# 14_-RGMII_PHY.net
KiCad netlist of a schematic drawn in Altium Designer
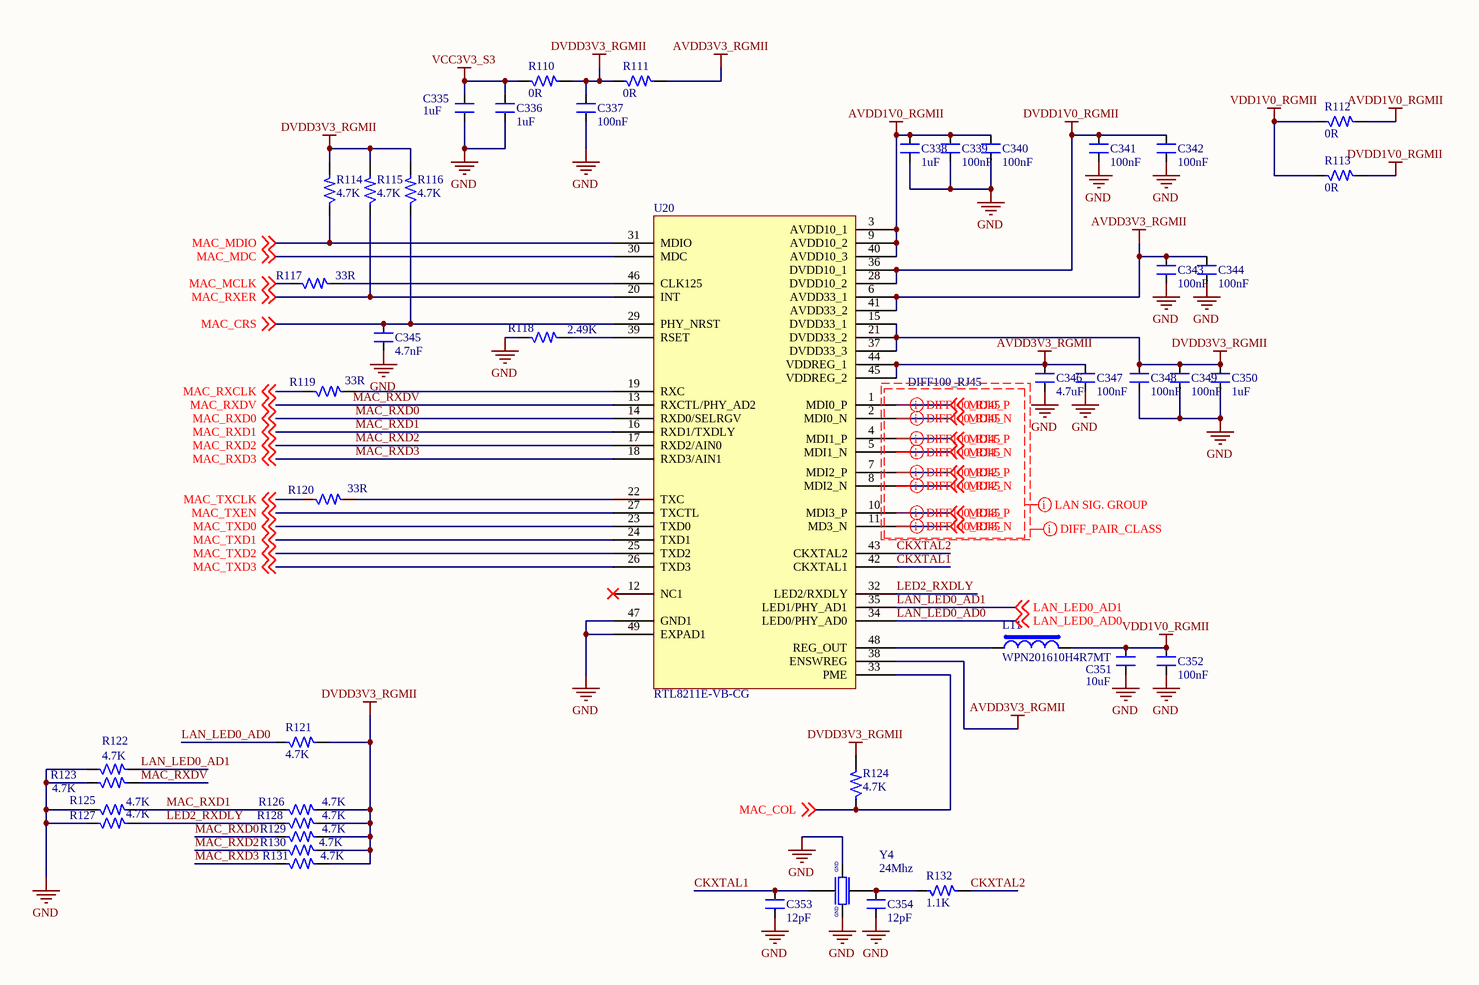
[diagram p0: [14]-RGMII_PHY.SchDoc]

(export (version "E")
  (design (tool "Eeschema 10.0.6"))
  (components
    (comp (ref "C335")
      (value "1uF")
      (footprint "CAP_0201")
      (description "1µF ±20% 16V Ceramic Capacitor X5R 0201 (0603 Metric)")
      (fields
        (field (name "MANUFACTURER") "Samsung Electro-Mechanics")
        (field (name "MANUFACTURER PART NUMBER") "CL03A105MO3NRNH")
      )
      (libsource (lib "EsteemPCB_SOM_Course_intlib") (part "CAP_1uF-16V-10%-0201"))
    )
    (comp (ref "C336")
      (value "1uF")
      (footprint "CAP_0201")
      (description "1µF ±20% 16V Ceramic Capacitor X5R 0201 (0603 Metric)")
      (fields
        (field (name "MANUFACTURER") "Samsung Electro-Mechanics")
        (field (name "MANUFACTURER PART NUMBER") "CL03A105MO3NRNH")
      )
      (libsource (lib "EsteemPCB_SOM_Course_intlib") (part "CAP_1uF-16V-10%-0201"))
    )
    (comp (ref "C337")
      (value "100nF")
      (footprint "CAP_0201")
      (description "0.1µF ±10% 25V Ceramic Capacitor X5R 0201 (0603 Metric)")
      (fields
        (field (name "MANUFACTURER") "TDK Corporation")
        (field (name "MANUFACTURER PART NUMBER") "C0603X5R1E104K030BB")
      )
      (libsource (lib "EsteemPCB_SOM_Course_intlib") (part "CAP_100nF-25V-10%-0201"))
    )
    (comp (ref "C338")
      (value "1uF")
      (footprint "CAP_0201")
      (description "1µF ±20% 16V Ceramic Capacitor X5R 0201 (0603 Metric)")
      (fields
        (field (name "MANUFACTURER") "Samsung Electro-Mechanics")
        (field (name "MANUFACTURER PART NUMBER") "CL03A105MO3NRNH")
      )
      (libsource (lib "EsteemPCB_SOM_Course_intlib") (part "CAP_1uF-16V-10%-0201"))
    )
    (comp (ref "C339")
      (value "100nF")
      (footprint "CAP_0201")
      (description "0.1µF ±10% 25V Ceramic Capacitor X5R 0201 (0603 Metric)")
      (fields
        (field (name "MANUFACTURER") "TDK Corporation")
        (field (name "MANUFACTURER PART NUMBER") "C0603X5R1E104K030BB")
      )
      (libsource (lib "EsteemPCB_SOM_Course_intlib") (part "CAP_100nF-25V-10%-0201"))
    )
    (comp (ref "C340")
      (value "100nF")
      (footprint "CAP_0201")
      (description "0.1µF ±10% 25V Ceramic Capacitor X5R 0201 (0603 Metric)")
      (fields
        (field (name "MANUFACTURER") "TDK Corporation")
        (field (name "MANUFACTURER PART NUMBER") "C0603X5R1E104K030BB")
      )
      (libsource (lib "EsteemPCB_SOM_Course_intlib") (part "CAP_100nF-25V-10%-0201"))
    )
    (comp (ref "C341")
      (value "100nF")
      (footprint "CAP_0201")
      (description "0.1µF ±10% 25V Ceramic Capacitor X5R 0201 (0603 Metric)")
      (fields
        (field (name "MANUFACTURER") "TDK Corporation")
        (field (name "MANUFACTURER PART NUMBER") "C0603X5R1E104K030BB")
      )
      (libsource (lib "EsteemPCB_SOM_Course_intlib") (part "CAP_100nF-25V-10%-0201"))
    )
    (comp (ref "C342")
      (value "100nF")
      (footprint "CAP_0201")
      (description "0.1µF ±10% 25V Ceramic Capacitor X5R 0201 (0603 Metric)")
      (fields
        (field (name "MANUFACTURER") "TDK Corporation")
        (field (name "MANUFACTURER PART NUMBER") "C0603X5R1E104K030BB")
      )
      (libsource (lib "EsteemPCB_SOM_Course_intlib") (part "CAP_100nF-25V-10%-0201"))
    )
    (comp (ref "C343")
      (value "100nF")
      (footprint "CAP_0201")
      (description "0.1µF ±10% 25V Ceramic Capacitor X5R 0201 (0603 Metric)")
      (fields
        (field (name "MANUFACTURER") "TDK Corporation")
        (field (name "MANUFACTURER PART NUMBER") "C0603X5R1E104K030BB")
      )
      (libsource (lib "EsteemPCB_SOM_Course_intlib") (part "CAP_100nF-25V-10%-0201"))
    )
    (comp (ref "C344")
      (value "100nF")
      (footprint "CAP_0201")
      (description "0.1µF ±10% 25V Ceramic Capacitor X5R 0201 (0603 Metric)")
      (fields
        (field (name "MANUFACTURER") "TDK Corporation")
        (field (name "MANUFACTURER PART NUMBER") "C0603X5R1E104K030BB")
      )
      (libsource (lib "EsteemPCB_SOM_Course_intlib") (part "CAP_100nF-25V-10%-0201"))
    )
    (comp (ref "C345")
      (value "4.7nF")
      (footprint "CAP_0201")
      (description "4700pF ±10% 10V Ceramic Capacitor X7R 0201 (0603 Metric)")
      (fields
        (field (name "MANUFACTURER") "AVX Corporation")
        (field (name "MANUFACTURER PART NUMBER") "0201ZC472KAT2A")
      )
      (libsource (lib "EsteemPCB_SOM_Course_intlib") (part "CAP_4.7nF-10V-10%-0201"))
    )
    (comp (ref "C346")
      (value "4.7uF")
      (footprint "CAP_0201")
      (description "4.7µF ±20% 6.3V Ceramic Capacitor X5R 0201 (0603 Metric)")
      (fields
        (field (name "MANUFACTURER") "Murata Electronics")
        (field (name "MANUFACTURER PART NUMBER") "GRM035R60J475ME15D")
      )
      (libsource (lib "EsteemPCB_SOM_Course_intlib") (part "CAP_4.7uF-6.3V-20%-0201"))
    )
    (comp (ref "C347")
      (value "100nF")
      (footprint "CAP_0201")
      (description "0.1µF ±10% 25V Ceramic Capacitor X5R 0201 (0603 Metric)")
      (fields
        (field (name "MANUFACTURER") "TDK Corporation")
        (field (name "MANUFACTURER PART NUMBER") "C0603X5R1E104K030BB")
      )
      (libsource (lib "EsteemPCB_SOM_Course_intlib") (part "CAP_100nF-25V-10%-0201"))
    )
    (comp (ref "C348")
      (value "100nF")
      (footprint "CAP_0201")
      (description "0.1µF ±10% 25V Ceramic Capacitor X5R 0201 (0603 Metric)")
      (fields
        (field (name "MANUFACTURER") "TDK Corporation")
        (field (name "MANUFACTURER PART NUMBER") "C0603X5R1E104K030BB")
      )
      (libsource (lib "EsteemPCB_SOM_Course_intlib") (part "CAP_100nF-25V-10%-0201"))
    )
    (comp (ref "C349")
      (value "100nF")
      (footprint "CAP_0201")
      (description "0.1µF ±10% 25V Ceramic Capacitor X5R 0201 (0603 Metric)")
      (fields
        (field (name "MANUFACTURER") "TDK Corporation")
        (field (name "MANUFACTURER PART NUMBER") "C0603X5R1E104K030BB")
      )
      (libsource (lib "EsteemPCB_SOM_Course_intlib") (part "CAP_100nF-25V-10%-0201"))
    )
    (comp (ref "C350")
      (value "1uF")
      (footprint "CAP_0603")
      (description "1µF ±10% 10V Ceramic Capacitor X5R 0603 (1608 Metric)")
      (fields
        (field (name "MANUFACTURER") "Samsung Electro-Mechanics")
        (field (name "MANUFACTURER PART NUMBER") "CL10A105KP8NNNC")
      )
      (libsource (lib "RK3399 _Module_Schlib") (part "CAP_1uF-10V-5%-0603"))
    )
    (comp (ref "C351")
      (value "10uF")
      (footprint "CAP_0402")
      (description "10µF ±20% 10V Ceramic Capacitor X5R 0402 (1005 Metric)")
      (fields
        (field (name "MANUFACTURER PART NUMBER") "CL05A106MP5NUNC")
        (field (name "MANUFACTURER") "Samsung Electro-Mechanics")
      )
      (libsource (lib "EsteemPCB_SOM_Course_intlib") (part "CAP_10uF-10V-20%-0402"))
    )
    (comp (ref "C352")
      (value "100nF")
      (footprint "CAP_0201")
      (description "0.1µF ±10% 25V Ceramic Capacitor X5R 0201 (0603 Metric)")
      (fields
        (field (name "MANUFACTURER") "TDK Corporation")
        (field (name "MANUFACTURER PART NUMBER") "C0603X5R1E104K030BB")
      )
      (libsource (lib "EsteemPCB_SOM_Course_intlib") (part "CAP_100nF-25V-10%-0201"))
    )
    (comp (ref "C353")
      (value "12pF")
      (footprint "CAP_0201")
      (description "12pF ±10% 16V Ceramic Capacitor C0G, NP0 0201 (0603 Metric)")
      (fields
        (field (name "MANUFACTURER") "AVX Corporation")
        (field (name "MANUFACTURER PART NUMBER") "0201YA120KAT2A")
      )
      (libsource (lib "EsteemPCB_SOM_Course_intlib") (part "CAP_12pF-16V-10%-0201"))
    )
    (comp (ref "C354")
      (value "12pF")
      (footprint "CAP_0201")
      (description "12pF ±10% 16V Ceramic Capacitor C0G, NP0 0201 (0603 Metric)")
      (fields
        (field (name "MANUFACTURER") "AVX Corporation")
        (field (name "MANUFACTURER PART NUMBER") "0201YA120KAT2A")
      )
      (libsource (lib "EsteemPCB_SOM_Course_intlib") (part "CAP_12pF-16V-10%-0201"))
    )
    (comp (ref "L11")
      (value "WPN201610H4R7MT")
      (footprint "IND_62.9_110X86.6_SMD")
      (description "4.7uH ±20% 900mA 425mΩ SMD,2.0x1.6x1.0mm Power Inductors RoHS")
      (fields (field (name "MANUFACTURER") "Sunlord"))
      (libsource (lib "RK3399 _Module_Schlib") (part "IND_4.7uH-0.9A-20%-SMD"))
    )
    (comp (ref "R110")
      (value "0R")
      (footprint "RES_0201")
      (description "0 Ohms Jumper 0.05W, 1/20W Chip Resistor 0201 (0603 Metric) Automotive AEC-Q200 Thick Film")
      (fields
        (field (name "MANUFACTURER") "Bourns Inc.")
        (field (name "MANUFACTURER PART NUMBER") "CR0201AJ/-000GLF")
      )
      (libsource (lib "EsteemPCB_SOM_Course_intlib") (part "RES_0R-0.05W-1%-0201"))
    )
    (comp (ref "R111")
      (value "0R")
      (footprint "RES_0201")
      (description "0 Ohms Jumper 0.05W, 1/20W Chip Resistor 0201 (0603 Metric) Automotive AEC-Q200 Thick Film")
      (fields
        (field (name "MANUFACTURER") "Bourns Inc.")
        (field (name "MANUFACTURER PART NUMBER") "CR0201AJ/-000GLF")
      )
      (libsource (lib "EsteemPCB_SOM_Course_intlib") (part "RES_0R-0.05W-1%-0201"))
    )
    (comp (ref "R112")
      (value "0R")
      (footprint "RES_0201")
      (description "0 Ohms Jumper 0.05W, 1/20W Chip Resistor 0201 (0603 Metric) Automotive AEC-Q200 Thick Film")
      (fields
        (field (name "MANUFACTURER") "Bourns Inc.")
        (field (name "MANUFACTURER PART NUMBER") "CR0201AJ/-000GLF")
      )
      (libsource (lib "EsteemPCB_SOM_Course_intlib") (part "RES_0R-0.05W-1%-0201"))
    )
    (comp (ref "R113")
      (value "0R")
      (footprint "RES_0201")
      (description "0 Ohms Jumper 0.05W, 1/20W Chip Resistor 0201 (0603 Metric) Automotive AEC-Q200 Thick Film")
      (fields
        (field (name "MANUFACTURER") "Bourns Inc.")
        (field (name "MANUFACTURER PART NUMBER") "CR0201AJ/-000GLF")
      )
      (libsource (lib "EsteemPCB_SOM_Course_intlib") (part "RES_0R-0.05W-1%-0201"))
    )
    (comp (ref "R114")
      (value "4.7K")
      (footprint "RES_0201")
      (description "4.02 kOhms ±1% 0.05W, 1/20W Chip Resistor 0201 (0603 Metric) Thick Film")
      (fields
        (field (name "MANUFACTURER") "Yageo")
        (field (name "MANUFACTURER PART NUMBER") "RC0201FR-074K02L")
      )
      (libsource (lib "EsteemPCB_SOM_Course_intlib") (part "RES_4.7K-0.1W-1%-0201"))
    )
    (comp (ref "R115")
      (value "4.7K")
      (footprint "RES_0201")
      (description "4.02 kOhms ±1% 0.05W, 1/20W Chip Resistor 0201 (0603 Metric) Thick Film")
      (fields
        (field (name "MANUFACTURER") "Yageo")
        (field (name "MANUFACTURER PART NUMBER") "RC0201FR-074K02L")
      )
      (libsource (lib "EsteemPCB_SOM_Course_intlib") (part "RES_4.7K-0.1W-1%-0201"))
    )
    (comp (ref "R116")
      (value "4.7K")
      (footprint "RES_0201")
      (description "4.02 kOhms ±1% 0.05W, 1/20W Chip Resistor 0201 (0603 Metric) Thick Film")
      (fields
        (field (name "MANUFACTURER") "Yageo")
        (field (name "MANUFACTURER PART NUMBER") "RC0201FR-074K02L")
      )
      (libsource (lib "EsteemPCB_SOM_Course_intlib") (part "RES_4.7K-0.1W-1%-0201"))
    )
    (comp (ref "R117")
      (value "33R")
      (footprint "RES_0201")
      (description "33 Ohms ±1% 0.05W, 1/20W Chip Resistor 0201 (0603 Metric) Thick Film")
      (fields
        (field (name "MANUFACTURER") "Yageo")
        (field (name "MANUFACTURER PART NUMBER") "RC0201FR-0733RL")
      )
      (libsource (lib "EsteemPCB_SOM_Course_intlib") (part "RES_33R-0.05W-1%-0201"))
    )
    (comp (ref "R118")
      (value "2.49K")
      (footprint "RES_0201")
      (description "2.49 kOhms ±1% 0.05W, 1/20W Chip Resistor 0201 (0603 Metric) Automotive AEC-Q200 Thick Film")
      (fields
        (field (name "MANUFACTURER") "Panasonic Electronic Components")
        (field (name "MANUFACTURER PART NUMBER") "ERJ-1GNF2491C")
      )
      (libsource (lib "EsteemPCB_SOM_Course_intlib") (part "RES_2.49K-0.05W-1%-0201"))
    )
    (comp (ref "R119")
      (value "33R")
      (footprint "RES_0201")
      (description "33 Ohms ±1% 0.05W, 1/20W Chip Resistor 0201 (0603 Metric) Thick Film")
      (fields
        (field (name "MANUFACTURER") "Yageo")
        (field (name "MANUFACTURER PART NUMBER") "RC0201FR-0733RL")
      )
      (libsource (lib "EsteemPCB_SOM_Course_intlib") (part "RES_33R-0.05W-1%-0201"))
    )
    (comp (ref "R120")
      (value "33R")
      (footprint "RES_0201")
      (description "33 Ohms ±1% 0.05W, 1/20W Chip Resistor 0201 (0603 Metric) Thick Film")
      (fields
        (field (name "MANUFACTURER") "Yageo")
        (field (name "MANUFACTURER PART NUMBER") "RC0201FR-0733RL")
      )
      (libsource (lib "EsteemPCB_SOM_Course_intlib") (part "RES_33R-0.05W-1%-0201"))
    )
    (comp (ref "R121")
      (value "4.7K")
      (footprint "RES_0201")
      (description "4.02 kOhms ±1% 0.05W, 1/20W Chip Resistor 0201 (0603 Metric) Thick Film")
      (fields
        (field (name "MANUFACTURER") "Yageo")
        (field (name "MANUFACTURER PART NUMBER") "RC0201FR-074K02L")
      )
      (libsource (lib "EsteemPCB_SOM_Course_intlib") (part "RES_4.7K-0.1W-1%-0201"))
    )
    (comp (ref "R122")
      (value "4.7K")
      (footprint "RES_0201")
      (description "4.02 kOhms ±1% 0.05W, 1/20W Chip Resistor 0201 (0603 Metric) Thick Film")
      (fields
        (field (name "MANUFACTURER") "Yageo")
        (field (name "MANUFACTURER PART NUMBER") "RC0201FR-074K02L")
      )
      (libsource (lib "EsteemPCB_SOM_Course_intlib") (part "RES_4.7K-0.1W-1%-0201"))
    )
    (comp (ref "R123")
      (value "4.7K")
      (footprint "RES_0201")
      (description "4.02 kOhms ±1% 0.05W, 1/20W Chip Resistor 0201 (0603 Metric) Thick Film")
      (fields
        (field (name "MANUFACTURER") "Yageo")
        (field (name "MANUFACTURER PART NUMBER") "RC0201FR-074K02L")
      )
      (libsource (lib "EsteemPCB_SOM_Course_intlib") (part "RES_4.7K-0.1W-1%-0201"))
    )
    (comp (ref "R124")
      (value "4.7K")
      (footprint "RES_0201")
      (description "4.02 kOhms ±1% 0.05W, 1/20W Chip Resistor 0201 (0603 Metric) Thick Film")
      (fields
        (field (name "MANUFACTURER") "Yageo")
        (field (name "MANUFACTURER PART NUMBER") "RC0201FR-074K02L")
      )
      (libsource (lib "EsteemPCB_SOM_Course_intlib") (part "RES_4.7K-0.1W-1%-0201"))
    )
    (comp (ref "R125")
      (value "4.7K")
      (footprint "RES_0201")
      (description "4.02 kOhms ±1% 0.05W, 1/20W Chip Resistor 0201 (0603 Metric) Thick Film")
      (fields
        (field (name "MANUFACTURER") "Yageo")
        (field (name "MANUFACTURER PART NUMBER") "RC0201FR-074K02L")
      )
      (libsource (lib "EsteemPCB_SOM_Course_intlib") (part "RES_4.7K-0.1W-1%-0201"))
    )
    (comp (ref "R126")
      (value "4.7K")
      (footprint "RES_0201")
      (description "4.02 kOhms ±1% 0.05W, 1/20W Chip Resistor 0201 (0603 Metric) Thick Film")
      (fields
        (field (name "MANUFACTURER") "Yageo")
        (field (name "MANUFACTURER PART NUMBER") "RC0201FR-074K02L")
      )
      (libsource (lib "EsteemPCB_SOM_Course_intlib") (part "RES_4.7K-0.1W-1%-0201"))
    )
    (comp (ref "R127")
      (value "4.7K")
      (footprint "RES_0201")
      (description "4.02 kOhms ±1% 0.05W, 1/20W Chip Resistor 0201 (0603 Metric) Thick Film")
      (fields
        (field (name "MANUFACTURER") "Yageo")
        (field (name "MANUFACTURER PART NUMBER") "RC0201FR-074K02L")
      )
      (libsource (lib "EsteemPCB_SOM_Course_intlib") (part "RES_4.7K-0.1W-1%-0201"))
    )
    (comp (ref "R128")
      (value "4.7K")
      (footprint "RES_0201")
      (description "4.02 kOhms ±1% 0.05W, 1/20W Chip Resistor 0201 (0603 Metric) Thick Film")
      (fields
        (field (name "MANUFACTURER") "Yageo")
        (field (name "MANUFACTURER PART NUMBER") "RC0201FR-074K02L")
      )
      (libsource (lib "EsteemPCB_SOM_Course_intlib") (part "RES_4.7K-0.1W-1%-0201"))
    )
    (comp (ref "R129")
      (value "4.7K")
      (footprint "RES_0201")
      (description "4.02 kOhms ±1% 0.05W, 1/20W Chip Resistor 0201 (0603 Metric) Thick Film")
      (fields
        (field (name "MANUFACTURER") "Yageo")
        (field (name "MANUFACTURER PART NUMBER") "RC0201FR-074K02L")
      )
      (libsource (lib "EsteemPCB_SOM_Course_intlib") (part "RES_4.7K-0.1W-1%-0201"))
    )
    (comp (ref "R130")
      (value "4.7K")
      (footprint "RES_0201")
      (description "4.02 kOhms ±1% 0.05W, 1/20W Chip Resistor 0201 (0603 Metric) Thick Film")
      (fields
        (field (name "MANUFACTURER") "Yageo")
        (field (name "MANUFACTURER PART NUMBER") "RC0201FR-074K02L")
      )
      (libsource (lib "EsteemPCB_SOM_Course_intlib") (part "RES_4.7K-0.1W-1%-0201"))
    )
    (comp (ref "R131")
      (value "4.7K")
      (footprint "RES_0201")
      (description "4.02 kOhms ±1% 0.05W, 1/20W Chip Resistor 0201 (0603 Metric) Thick Film")
      (fields
        (field (name "MANUFACTURER") "Yageo")
        (field (name "MANUFACTURER PART NUMBER") "RC0201FR-074K02L")
      )
      (libsource (lib "EsteemPCB_SOM_Course_intlib") (part "RES_4.7K-0.1W-1%-0201"))
    )
    (comp (ref "R132")
      (value "1.1K")
      (footprint "RES_0201")
      (description "1.1 kOhms ±1% 0.05W, 1/20W Chip Resistor 0201 (0603 Metric) Automotive AEC-Q200 Thick Film")
      (fields
        (field (name "MANUFACTURER") "Panasonic Electronic Components")
        (field (name "MANUFACTURER PART NUMBER") "ERJ-1GNF1101C")
      )
      (libsource (lib "EsteemPCB_SOM_Course_intlib") (part "RES_1.1K-0.05W-1%-0201"))
    )
    (comp (ref "U20")
      (value "RTL8211E-VB-CG")
      (footprint "QFN48_19.6_324X324_SMD")
      (fields (field (name "MANUFACTURER") "Realtek Semicon"))
      (libsource (lib "RK3399 _Module_Schlib") (part "IC_RTL8211E-VB-CG"))
    )
    (comp (ref "Y4")
      (value "24Mhz")
      (footprint "XTAL_ABM8AIG-24.000MHZ-12-2Z-T3")
      (description "24MHz ±20ppm Crystal 12pF 50 Ohms 4-SMD, No Lead")
      (fields
        (field (name "MANUFACTURER") "Abracon LLC")
        (field (name "MANUFACTURER PART NUMBER") "ABM8AIG-24.000MHZ-12-2Z-T3")
      )
      (libsource (lib "RK3399 _Module_Schlib") (part "XTAL_24Mhz-12pF-4-SMD"))
    )
  )
  (nets
    (net (code "1") (name "/CKXTAL1") (class "Default")
      (node (ref "C353") (pin "2") (pinfunction "2_2") (pintype "passive"))
      (node (ref "U20") (pin "42") (pinfunction "CKXTAL1_42") (pintype "passive"))
      (node (ref "Y4") (pin "1") (pinfunction "1_1") (pintype "passive"))
    )
    (net (code "2") (name "/CKXTAL2") (class "Default")
      (node (ref "R132") (pin "2") (pinfunction "2_2") (pintype "passive"))
      (node (ref "U20") (pin "43") (pinfunction "CKXTAL2_43") (pintype "passive"))
    )
    (net (code "3") (name "/LED2_RXDLY") (class "Default")
      (node (ref "R127") (pin "2") (pinfunction "2_2") (pintype "passive"))
      (node (ref "R128") (pin "1") (pinfunction "1_1") (pintype "passive"))
      (node (ref "U20") (pin "32") (pinfunction "LED2/RXDLY_32") (pintype "passive"))
    )
    (net (code "4") (name "AVDD1V0_RGMII") (class "Default")
      (node (ref "C338") (pin "2") (pinfunction "2_2") (pintype "passive"))
      (node (ref "C339") (pin "2") (pinfunction "2_2") (pintype "passive"))
      (node (ref "C340") (pin "2") (pinfunction "2_2") (pintype "passive"))
      (node (ref "R112") (pin "2") (pinfunction "2_2") (pintype "passive"))
      (node (ref "U20") (pin "3") (pinfunction "AVDD10_1_3") (pintype "passive"))
      (node (ref "U20") (pin "40") (pinfunction "AVDD10_3_40") (pintype "passive"))
      (node (ref "U20") (pin "9") (pinfunction "AVDD10_2_9") (pintype "passive"))
    )
    (net (code "5") (name "AVDD3V3_RGMII") (class "Default")
      (node (ref "C343") (pin "2") (pinfunction "2_2") (pintype "passive"))
      (node (ref "C344") (pin "2") (pinfunction "2_2") (pintype "passive"))
      (node (ref "C346") (pin "2") (pinfunction "2_2") (pintype "passive"))
      (node (ref "C347") (pin "2") (pinfunction "2_2") (pintype "passive"))
      (node (ref "R111") (pin "2") (pinfunction "2_2") (pintype "passive"))
      (node (ref "U20") (pin "38") (pinfunction "ENSWREG_38") (pintype "passive"))
      (node (ref "U20") (pin "41") (pinfunction "AVDD33_2_41") (pintype "passive"))
      (node (ref "U20") (pin "44") (pinfunction "VDDREG_1_44") (pintype "passive"))
      (node (ref "U20") (pin "45") (pinfunction "VDDREG_2_45") (pintype "passive"))
      (node (ref "U20") (pin "6") (pinfunction "AVDD33_1_6") (pintype "passive"))
    )
    (net (code "6") (name "DVDD1V0_RGMII") (class "Default")
      (node (ref "C341") (pin "2") (pinfunction "2_2") (pintype "passive"))
      (node (ref "C342") (pin "2") (pinfunction "2_2") (pintype "passive"))
      (node (ref "R113") (pin "2") (pinfunction "2_2") (pintype "passive"))
      (node (ref "U20") (pin "28") (pinfunction "DVDD10_2_28") (pintype "passive"))
      (node (ref "U20") (pin "36") (pinfunction "DVDD10_1_36") (pintype "passive"))
    )
    (net (code "7") (name "DVDD3V3_RGMII") (class "Default")
      (node (ref "C337") (pin "2") (pinfunction "2_2") (pintype "passive"))
      (node (ref "C348") (pin "2") (pinfunction "2_2") (pintype "passive"))
      (node (ref "C349") (pin "2") (pinfunction "2_2") (pintype "passive"))
      (node (ref "C350") (pin "2") (pinfunction "2_2") (pintype "passive"))
      (node (ref "R110") (pin "2") (pinfunction "2_2") (pintype "passive"))
      (node (ref "R111") (pin "1") (pinfunction "1_1") (pintype "passive"))
      (node (ref "R114") (pin "2") (pinfunction "2_2") (pintype "passive"))
      (node (ref "R115") (pin "2") (pinfunction "2_2") (pintype "passive"))
      (node (ref "R116") (pin "2") (pinfunction "2_2") (pintype "passive"))
      (node (ref "R121") (pin "2") (pinfunction "2_2") (pintype "passive"))
      (node (ref "R124") (pin "2") (pinfunction "2_2") (pintype "passive"))
      (node (ref "R126") (pin "2") (pinfunction "2_2") (pintype "passive"))
      (node (ref "R128") (pin "2") (pinfunction "2_2") (pintype "passive"))
      (node (ref "R129") (pin "2") (pinfunction "2_2") (pintype "passive"))
      (node (ref "R130") (pin "2") (pinfunction "2_2") (pintype "passive"))
      (node (ref "R131") (pin "2") (pinfunction "2_2") (pintype "passive"))
      (node (ref "U20") (pin "15") (pinfunction "DVDD33_1_15") (pintype "passive"))
      (node (ref "U20") (pin "21") (pinfunction "DVDD33_2_21") (pintype "passive"))
      (node (ref "U20") (pin "37") (pinfunction "DVDD33_3_37") (pintype "passive"))
    )
    (net (code "8") (name "GND") (class "Default")
      (node (ref "C335") (pin "1") (pinfunction "1_1") (pintype "passive"))
      (node (ref "C336") (pin "1") (pinfunction "1_1") (pintype "passive"))
      (node (ref "C337") (pin "1") (pinfunction "1_1") (pintype "passive"))
      (node (ref "C338") (pin "1") (pinfunction "1_1") (pintype "passive"))
      (node (ref "C339") (pin "1") (pinfunction "1_1") (pintype "passive"))
      (node (ref "C340") (pin "1") (pinfunction "1_1") (pintype "passive"))
      (node (ref "C341") (pin "1") (pinfunction "1_1") (pintype "passive"))
      (node (ref "C342") (pin "1") (pinfunction "1_1") (pintype "passive"))
      (node (ref "C343") (pin "1") (pinfunction "1_1") (pintype "passive"))
      (node (ref "C344") (pin "1") (pinfunction "1_1") (pintype "passive"))
      (node (ref "C345") (pin "1") (pinfunction "1_1") (pintype "passive"))
      (node (ref "C346") (pin "1") (pinfunction "1_1") (pintype "passive"))
      (node (ref "C347") (pin "1") (pinfunction "1_1") (pintype "passive"))
      (node (ref "C348") (pin "1") (pinfunction "1_1") (pintype "passive"))
      (node (ref "C349") (pin "1") (pinfunction "1_1") (pintype "passive"))
      (node (ref "C350") (pin "1") (pinfunction "1_1") (pintype "passive"))
      (node (ref "C351") (pin "1") (pinfunction "1_1") (pintype "passive"))
      (node (ref "C352") (pin "1") (pinfunction "1_1") (pintype "passive"))
      (node (ref "C353") (pin "1") (pinfunction "1_1") (pintype "passive"))
      (node (ref "C354") (pin "1") (pinfunction "1_1") (pintype "passive"))
      (node (ref "R118") (pin "1") (pinfunction "1_1") (pintype "passive"))
      (node (ref "R122") (pin "1") (pinfunction "1_1") (pintype "passive"))
      (node (ref "R123") (pin "1") (pinfunction "1_1") (pintype "passive"))
      (node (ref "R125") (pin "1") (pinfunction "1_1") (pintype "passive"))
      (node (ref "R127") (pin "1") (pinfunction "1_1") (pintype "passive"))
      (node (ref "U20") (pin "47") (pinfunction "GND1_47") (pintype "passive"))
      (node (ref "U20") (pin "49") (pinfunction "EXPAD1_49") (pintype "passive"))
      (node (ref "Y4") (pin "2") (pinfunction "2_2") (pintype "passive"))
      (node (ref "Y4") (pin "4") (pinfunction "4_4") (pintype "passive"))
    )
    (net (code "9") (name "LAN_LED0_AD0") (class "Default")
      (node (ref "R121") (pin "1") (pinfunction "1_1") (pintype "passive"))
      (node (ref "U20") (pin "34") (pinfunction "LED0/PHY_AD0_34") (pintype "passive"))
    )
    (net (code "10") (name "LAN_LED0_AD1") (class "Default")
      (node (ref "R122") (pin "2") (pinfunction "2_2") (pintype "passive"))
      (node (ref "U20") (pin "35") (pinfunction "LED1/PHY_AD1_35") (pintype "passive"))
    )
    (net (code "11") (name "MAC_COL") (class "Default")
      (node (ref "R124") (pin "1") (pinfunction "1_1") (pintype "passive"))
      (node (ref "U20") (pin "33") (pinfunction "PME_33") (pintype "passive"))
    )
    (net (code "12") (name "MAC_CRS") (class "Default")
      (node (ref "C345") (pin "2") (pinfunction "2_2") (pintype "passive"))
      (node (ref "R116") (pin "1") (pinfunction "1_1") (pintype "passive"))
      (node (ref "U20") (pin "29") (pinfunction "PHY_NRST_29") (pintype "passive"))
    )
    (net (code "13") (name "MAC_MCLK") (class "Default")
      (node (ref "R117") (pin "1") (pinfunction "1_1") (pintype "passive"))
    )
    (net (code "14") (name "MAC_MDC") (class "Default")
      (node (ref "U20") (pin "30") (pinfunction "MDC_30") (pintype "passive"))
    )
    (net (code "15") (name "MAC_MDIO") (class "Default")
      (node (ref "R114") (pin "1") (pinfunction "1_1") (pintype "passive"))
      (node (ref "U20") (pin "31") (pinfunction "MDIO_31") (pintype "passive"))
    )
    (net (code "16") (name "MAC_RXCLK") (class "Default")
      (node (ref "R119") (pin "1") (pinfunction "1_1") (pintype "passive"))
    )
    (net (code "17") (name "MAC_RXD0") (class "Default")
      (node (ref "R129") (pin "1") (pinfunction "1_1") (pintype "passive"))
      (node (ref "U20") (pin "14") (pinfunction "RXD0/SELRGV_14") (pintype "passive"))
    )
    (net (code "18") (name "MAC_RXD1") (class "Default")
      (node (ref "R125") (pin "2") (pinfunction "2_2") (pintype "passive"))
      (node (ref "R126") (pin "1") (pinfunction "1_1") (pintype "passive"))
      (node (ref "U20") (pin "16") (pinfunction "RXD1/TXDLY_16") (pintype "passive"))
    )
    (net (code "19") (name "MAC_RXD2") (class "Default")
      (node (ref "R130") (pin "1") (pinfunction "1_1") (pintype "passive"))
      (node (ref "U20") (pin "17") (pinfunction "RXD2/AIN0_17") (pintype "passive"))
    )
    (net (code "20") (name "MAC_RXD3") (class "Default")
      (node (ref "R131") (pin "1") (pinfunction "1_1") (pintype "passive"))
      (node (ref "U20") (pin "18") (pinfunction "RXD3/AIN1_18") (pintype "passive"))
    )
    (net (code "21") (name "MAC_RXDV") (class "Default")
      (node (ref "R123") (pin "2") (pinfunction "2_2") (pintype "passive"))
      (node (ref "U20") (pin "13") (pinfunction "RXCTL/PHY_AD2_13") (pintype "passive"))
    )
    (net (code "22") (name "MAC_RXER") (class "Default")
      (node (ref "R115") (pin "1") (pinfunction "1_1") (pintype "passive"))
      (node (ref "U20") (pin "20") (pinfunction "INT_20") (pintype "passive"))
    )
    (net (code "23") (name "MAC_TXCLK") (class "Default")
      (node (ref "R120") (pin "1") (pinfunction "1_1") (pintype "passive"))
    )
    (net (code "24") (name "MAC_TXD0") (class "Default")
      (node (ref "U20") (pin "23") (pinfunction "TXD0_23") (pintype "passive"))
    )
    (net (code "25") (name "MAC_TXD1") (class "Default")
      (node (ref "U20") (pin "24") (pinfunction "TXD1_24") (pintype "passive"))
    )
    (net (code "26") (name "MAC_TXD2") (class "Default")
      (node (ref "U20") (pin "25") (pinfunction "TXD2_25") (pintype "passive"))
    )
    (net (code "27") (name "MAC_TXD3") (class "Default")
      (node (ref "U20") (pin "26") (pinfunction "TXD3_26") (pintype "passive"))
    )
    (net (code "28") (name "MAC_TXEN") (class "Default")
      (node (ref "U20") (pin "27") (pinfunction "TXCTL_27") (pintype "passive"))
    )
    (net (code "29") (name "MDI0_N") (class "Default")
      (node (ref "U20") (pin "2") (pinfunction "MDI0_N_2") (pintype "passive"))
    )
    (net (code "30") (name "MDI0_P") (class "Default")
      (node (ref "U20") (pin "1") (pinfunction "MDI0_P_1") (pintype "passive"))
    )
    (net (code "31") (name "MDI1_N") (class "Default")
      (node (ref "U20") (pin "5") (pinfunction "MDI1_N_5") (pintype "passive"))
    )
    (net (code "32") (name "MDI1_P") (class "Default")
      (node (ref "U20") (pin "4") (pinfunction "MDI1_P_4") (pintype "passive"))
    )
    (net (code "33") (name "MDI2_N") (class "Default")
      (node (ref "U20") (pin "8") (pinfunction "MDI2_N_8") (pintype "passive"))
    )
    (net (code "34") (name "MDI2_P") (class "Default")
      (node (ref "U20") (pin "7") (pinfunction "MDI2_P_7") (pintype "passive"))
    )
    (net (code "35") (name "MDI3_N") (class "Default")
      (node (ref "U20") (pin "11") (pinfunction "MD3_N_11") (pintype "passive"))
    )
    (net (code "36") (name "MDI3_P") (class "Default")
      (node (ref "U20") (pin "10") (pinfunction "MDI3_P_10") (pintype "passive"))
    )
    (net (code "37") (name "Net-(C354-Pad2)") (class "Default")
      (node (ref "C354") (pin "2") (pinfunction "2_2") (pintype "passive"))
      (node (ref "R132") (pin "1") (pinfunction "1_1") (pintype "passive"))
      (node (ref "Y4") (pin "3") (pinfunction "3_3") (pintype "passive"))
    )
    (net (code "38") (name "Net-(U20-CLK125)") (class "Default")
      (node (ref "R117") (pin "2") (pinfunction "2_2") (pintype "passive"))
      (node (ref "U20") (pin "46") (pinfunction "CLK125_46") (pintype "passive"))
    )
    (net (code "39") (name "Net-(U20-REG_OUT)") (class "Default")
      (node (ref "L11") (pin "1") (pinfunction "1_1") (pintype "passive"))
      (node (ref "U20") (pin "48") (pinfunction "REG_OUT_48") (pintype "passive"))
    )
    (net (code "40") (name "Net-(U20-RSET)") (class "Default")
      (node (ref "R118") (pin "2") (pinfunction "2_2") (pintype "passive"))
      (node (ref "U20") (pin "39") (pinfunction "RSET_39") (pintype "passive"))
    )
    (net (code "41") (name "Net-(U20-RXC)") (class "Default")
      (node (ref "R119") (pin "2") (pinfunction "2_2") (pintype "passive"))
      (node (ref "U20") (pin "19") (pinfunction "RXC_19") (pintype "passive"))
    )
    (net (code "42") (name "Net-(U20-TXC)") (class "Default")
      (node (ref "R120") (pin "2") (pinfunction "2_2") (pintype "passive"))
      (node (ref "U20") (pin "22") (pinfunction "TXC_22") (pintype "passive"))
    )
    (net (code "43") (name "VCC3V3_S3") (class "Default")
      (node (ref "C335") (pin "2") (pinfunction "2_2") (pintype "passive"))
      (node (ref "C336") (pin "2") (pinfunction "2_2") (pintype "passive"))
      (node (ref "R110") (pin "1") (pinfunction "1_1") (pintype "passive"))
    )
    (net (code "44") (name "VDD1V0_RGMII") (class "Default")
      (node (ref "C351") (pin "2") (pinfunction "2_2") (pintype "passive"))
      (node (ref "C352") (pin "2") (pinfunction "2_2") (pintype "passive"))
      (node (ref "L11") (pin "2") (pinfunction "2_2") (pintype "passive"))
      (node (ref "R112") (pin "1") (pinfunction "1_1") (pintype "passive"))
      (node (ref "R113") (pin "1") (pinfunction "1_1") (pintype "passive"))
    )
    (net (code "45") (name "unconnected-(U20-NC1-Pad12)") (class "Default")
      (node (ref "U20") (pin "12") (pinfunction "NC1_12") (pintype "passive+no_connect"))
    )
  )
)
